# Raspberry_pi_shild_v1-.net
KiCad netlist of a schematic drawn in EAGLE
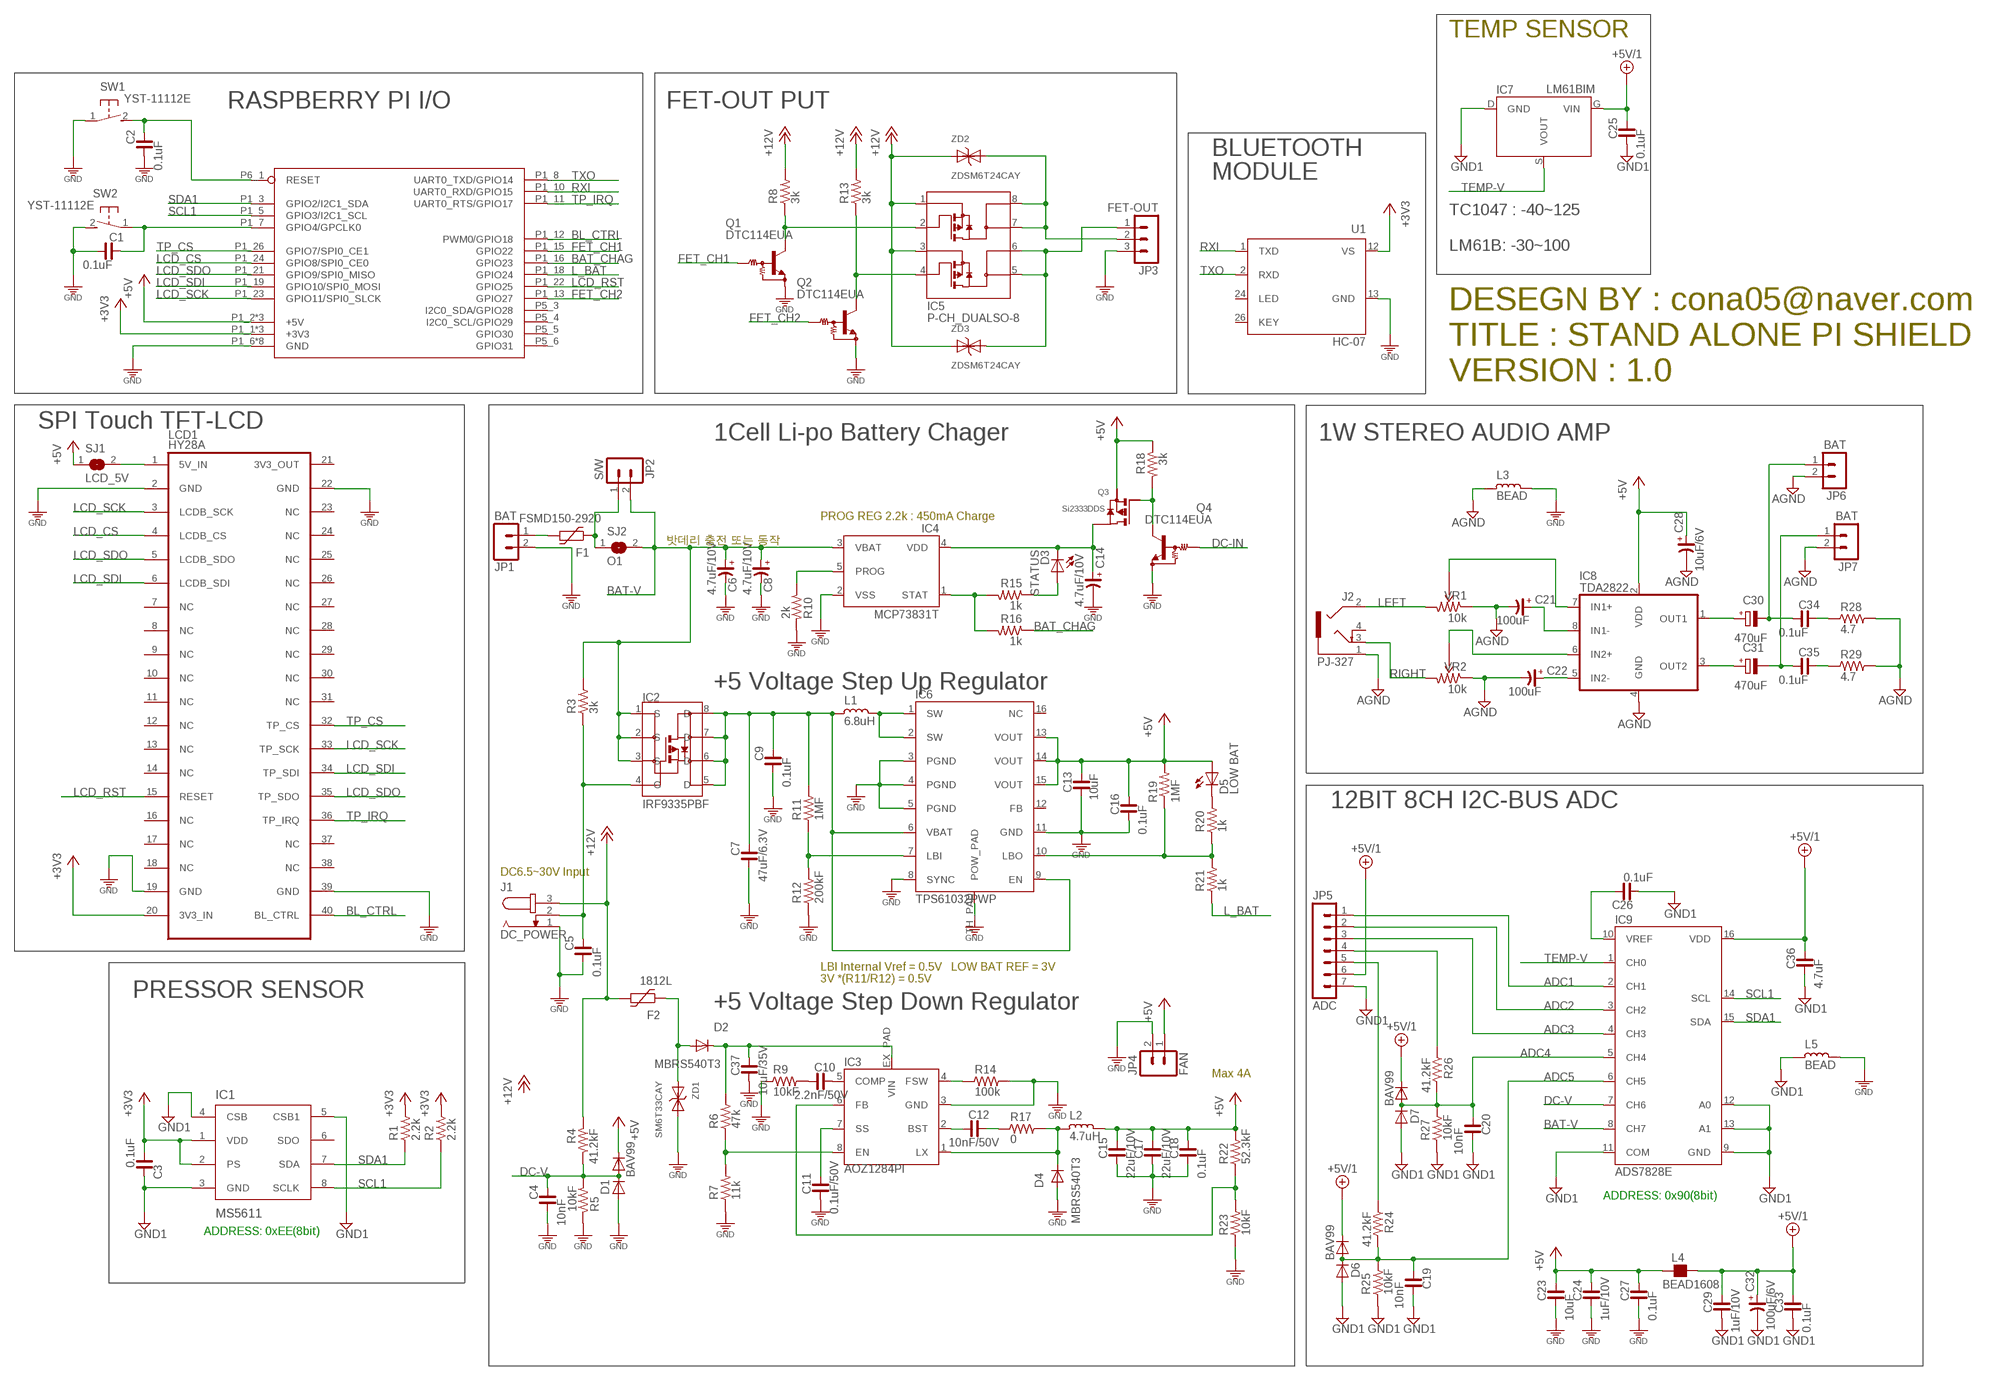
[diagram p0: schematic, sheet 1]

(export (version "E")
  (design (tool "Eeschema 10.0.6"))
  (components
    (comp (ref "C1")
      (value "0.1uF")
      (footprint "eagle-import:C0603")
      (libsource (lib "eagle-import") (part "C_0603"))
    )
    (comp (ref "C2")
      (value "0.1uF")
      (footprint "eagle-import:C0603")
      (libsource (lib "eagle-import") (part "C_0603"))
    )
    (comp (ref "C3")
      (value "0.1uF")
      (footprint "eagle-import:C0603")
      (libsource (lib "eagle-import") (part "C_0603"))
    )
    (comp (ref "C4")
      (value "10nF")
      (footprint "eagle-import:C0603")
      (libsource (lib "eagle-import") (part "C_0603"))
    )
    (comp (ref "C5")
      (value "0.1uF")
      (footprint "eagle-import:C0603")
      (libsource (lib "eagle-import") (part "C_0603"))
    )
    (comp (ref "C6")
      (value "4.7uF/10V")
      (footprint "eagle-import:C3216-18_T")
      (libsource (lib "eagle-import") (part "CP_3216-18"))
    )
    (comp (ref "C7")
      (value "47uF/6.3V")
      (footprint "eagle-import:C3216")
      (libsource (lib "eagle-import") (part "C_3216"))
    )
    (comp (ref "C8")
      (value "4.7uF/10V")
      (footprint "eagle-import:C3216-18_T")
      (libsource (lib "eagle-import") (part "CP_3216-18"))
    )
    (comp (ref "C9")
      (value "0.1uF")
      (footprint "eagle-import:C0603")
      (libsource (lib "eagle-import") (part "C_0603"))
    )
    (comp (ref "C10")
      (value "2.2nF/50V")
      (footprint "eagle-import:C0603")
      (libsource (lib "eagle-import") (part "C_0603"))
    )
    (comp (ref "C11")
      (value "0.1uF/50V")
      (footprint "eagle-import:C0603")
      (libsource (lib "eagle-import") (part "C_0603"))
    )
    (comp (ref "C12")
      (value "10nF/50V")
      (footprint "eagle-import:C0603")
      (libsource (lib "eagle-import") (part "C_0603"))
    )
    (comp (ref "C13")
      (value "10uF")
      (footprint "eagle-import:C2012")
      (libsource (lib "eagle-import") (part "C_2012"))
    )
    (comp (ref "C14")
      (value "4.7uF/10V")
      (footprint "eagle-import:C3216-18_T")
      (libsource (lib "eagle-import") (part "CP_3216-18"))
    )
    (comp (ref "C15")
      (value "22uF/10V")
      (footprint "eagle-import:C3216")
      (libsource (lib "eagle-import") (part "C_3216"))
    )
    (comp (ref "C16")
      (value "0.1uF")
      (footprint "eagle-import:C0603")
      (libsource (lib "eagle-import") (part "C_0603"))
    )
    (comp (ref "C17")
      (value "22uF/10V")
      (footprint "eagle-import:C3216")
      (libsource (lib "eagle-import") (part "C_3216"))
    )
    (comp (ref "C18")
      (value "0.1uF")
      (footprint "eagle-import:C0603")
      (libsource (lib "eagle-import") (part "C_0603"))
    )
    (comp (ref "C19")
      (value "10nF")
      (footprint "eagle-import:C0603")
      (libsource (lib "eagle-import") (part "C_0603"))
    )
    (comp (ref "C20")
      (value "10nF")
      (footprint "eagle-import:C0603")
      (libsource (lib "eagle-import") (part "C_0603"))
    )
    (comp (ref "C21")
      (value "100uF")
      (footprint "eagle-import:C3528-21_T")
      (libsource (lib "eagle-import") (part "CP_3528-21"))
    )
    (comp (ref "C22")
      (value "100uF")
      (footprint "eagle-import:C3528-21_T")
      (libsource (lib "eagle-import") (part "CP_3528-21"))
    )
    (comp (ref "C23")
      (value "10uF")
      (footprint "eagle-import:C0805")
      (libsource (lib "eagle-import") (part "C_0805"))
    )
    (comp (ref "C24")
      (value "1uF/10V")
      (footprint "eagle-import:C0603")
      (libsource (lib "eagle-import") (part "C_0603"))
    )
    (comp (ref "C25")
      (value "0.1uF")
      (footprint "eagle-import:C0603")
      (libsource (lib "eagle-import") (part "C_0603"))
    )
    (comp (ref "C26")
      (value "0.1uF")
      (footprint "eagle-import:C0603")
      (libsource (lib "eagle-import") (part "C_0603"))
    )
    (comp (ref "C27")
      (value "0.1uF")
      (footprint "eagle-import:C0603")
      (libsource (lib "eagle-import") (part "C_0603"))
    )
    (comp (ref "C28")
      (value "10uF/6V")
      (footprint "eagle-import:C3216-18_T")
      (libsource (lib "eagle-import") (part "CP_3216-18"))
    )
    (comp (ref "C29")
      (value "1uF/10V")
      (footprint "eagle-import:C0603")
      (libsource (lib "eagle-import") (part "C_0603"))
    )
    (comp (ref "C30")
      (value "470uF")
      (footprint "eagle-import:D_7343-31W")
      (libsource (lib "eagle-import") (part "CPOL-EUD/7343-31W"))
    )
    (comp (ref "C31")
      (value "470uF")
      (footprint "eagle-import:D_7343-31W")
      (libsource (lib "eagle-import") (part "CPOL-EUD/7343-31W"))
    )
    (comp (ref "C32")
      (value "100uF/6V")
      (footprint "eagle-import:C3528-21_T")
      (libsource (lib "eagle-import") (part "CP_3528-21"))
    )
    (comp (ref "C33")
      (value "0.1uF")
      (footprint "eagle-import:C0603")
      (libsource (lib "eagle-import") (part "C_0603"))
    )
    (comp (ref "C34")
      (value "0.1uF")
      (footprint "eagle-import:C0603")
      (libsource (lib "eagle-import") (part "C_0603"))
    )
    (comp (ref "C35")
      (value "0.1uF")
      (footprint "eagle-import:C0603")
      (libsource (lib "eagle-import") (part "C_0603"))
    )
    (comp (ref "C36")
      (value "4.7uF")
      (footprint "eagle-import:C0805")
      (libsource (lib "eagle-import") (part "C_0805"))
    )
    (comp (ref "C37")
      (value "10uF/35V")
      (footprint "eagle-import:C3225")
      (libsource (lib "eagle-import") (part "C_3225"))
    )
    (comp (ref "D1")
      (value "BAV99")
      (footprint "eagle-import:SOT23")
      (libsource (lib "eagle-import") (part "BAV99"))
    )
    (comp (ref "D2")
      (value "MBRS540T3")
      (footprint "eagle-import:SMC")
      (libsource (lib "eagle-import") (part "DIODE-SMC"))
    )
    (comp (ref "D3")
      (value "STATUS")
      (footprint "eagle-import:LED3MM")
      (libsource (lib "eagle-import") (part "LED3MM"))
    )
    (comp (ref "D4")
      (value "MBRS540T3")
      (footprint "eagle-import:SMC")
      (libsource (lib "eagle-import") (part "DIODE-SMC"))
    )
    (comp (ref "D5")
      (value "LOW BAT")
      (footprint "eagle-import:LED3MM")
      (libsource (lib "eagle-import") (part "LED3MM"))
    )
    (comp (ref "D6")
      (value "BAV99")
      (footprint "eagle-import:SOT23")
      (libsource (lib "eagle-import") (part "BAV99"))
    )
    (comp (ref "D7")
      (value "BAV99")
      (footprint "eagle-import:SOT23")
      (libsource (lib "eagle-import") (part "BAV99"))
    )
    (comp (ref "F1")
      (value "FSMD150-2920")
      (footprint "eagle-import:1812L")
      (libsource (lib "eagle-import") (part "1812L"))
    )
    (comp (ref "F2")
      (value "1812L")
      (footprint "eagle-import:1812L")
      (libsource (lib "eagle-import") (part "1812L"))
    )
    (comp (ref "IC1")
      (value "MS5611")
      (footprint "eagle-import:LCP8")
      (libsource (lib "eagle-import") (part "MS5611"))
    )
    (comp (ref "IC2")
      (value "IRF9335PBF")
      (footprint "eagle-import:SO08")
      (libsource (lib "eagle-import") (part "HEXFET_P"))
    )
    (comp (ref "IC3")
      (value "AOZ1284PI")
      (footprint "eagle-import:S08-EP1")
      (libsource (lib "eagle-import") (part "AOZ1284PI"))
    )
    (comp (ref "IC4")
      (value "MCP73831T")
      (footprint "eagle-import:SOT23-5L@1")
      (libsource (lib "eagle-import") (part "MCP73831T"))
    )
    (comp (ref "IC5")
      (value "P-CH_DUALSO-8")
      (footprint "eagle-import:SO08-1")
      (libsource (lib "eagle-import") (part "P-CH_DUALSO-8"))
    )
    (comp (ref "IC6")
      (value "TPS61032PWP")
      (footprint "eagle-import:R-PDSO-G16-TH_PAD")
      (libsource (lib "eagle-import") (part "TPS61032"))
    )
    (comp (ref "IC7")
      (value "LM61BIM")
      (footprint "eagle-import:SOT23")
      (libsource (lib "eagle-import") (part "LM61BIM"))
    )
    (comp (ref "IC8")
      (value "TDA2822")
      (footprint "eagle-import:SO08")
      (libsource (lib "eagle-import") (part "TDA2822"))
    )
    (comp (ref "IC9")
      (value "ADS7828E")
      (footprint "eagle-import:R-PDSO-G16")
      (libsource (lib "eagle-import") (part "ADS7828"))
    )
    (comp (ref "J1")
      (value "DC_POWER")
      (footprint "eagle-import:SPC4077")
      (libsource (lib "eagle-import") (part "JACK-PLUG0"))
    )
    (comp (ref "J2")
      (value "PJ-327")
      (footprint "eagle-import:PJ-327-2")
      (libsource (lib "eagle-import") (part "AUDIO_JACK2"))
    )
    (comp (ref "JP1")
      (value "BAT")
      (footprint "eagle-import:MA02-MOL-R")
      (libsource (lib "eagle-import") (part "MA02MOL-R"))
    )
    (comp (ref "JP2")
      (value "S/W")
      (footprint "eagle-import:MA02-MOL-R")
      (libsource (lib "eagle-import") (part "MA02MOL-R"))
    )
    (comp (ref "JP3")
      (value "FET-OUT")
      (footprint "eagle-import:MA03")
      (libsource (lib "eagle-import") (part "MA03-1DEF"))
    )
    (comp (ref "JP4")
      (value "FAN")
      (footprint "eagle-import:MA02-MOL-R")
      (libsource (lib "eagle-import") (part "MA02MOL-R"))
    )
    (comp (ref "JP5")
      (value "ADC")
      (footprint "eagle-import:MA07-1T")
      (libsource (lib "eagle-import") (part "MA07-1"))
    )
    (comp (ref "JP6")
      (value "BAT")
      (footprint "eagle-import:MA02-MOL-R")
      (libsource (lib "eagle-import") (part "MA02MOL-R"))
    )
    (comp (ref "JP7")
      (value "BAT")
      (footprint "eagle-import:MA02-MOL-R")
      (libsource (lib "eagle-import") (part "MA02MOL-R"))
    )
    (comp (ref "L1")
      (value "6.8uH")
      (footprint "eagle-import:L4545")
      (libsource (lib "eagle-import") (part "L_4545"))
    )
    (comp (ref "L2")
      (value "4.7uH")
      (footprint "eagle-import:L4545")
      (libsource (lib "eagle-import") (part "L_4545"))
    )
    (comp (ref "L3")
      (value "BEAD")
      (footprint "eagle-import:L0603")
      (libsource (lib "eagle-import") (part "L_0603"))
    )
    (comp (ref "L4")
      (value "BEAD1608")
      (footprint "eagle-import:L0603")
      (libsource (lib "eagle-import") (part "FB_0603"))
    )
    (comp (ref "L5")
      (value "BEAD")
      (footprint "eagle-import:L0603")
      (libsource (lib "eagle-import") (part "L_0603"))
    )
    (comp (ref "LCD1")
      (value "HY28A")
      (footprint "eagle-import:HY28A")
      (libsource (lib "eagle-import") (part "HY28A"))
    )
    (comp (ref "Q1")
      (value "DTC114EUA")
      (footprint "eagle-import:SC59-BEC")
      (libsource (lib "eagle-import") (part "DTC114EUA"))
    )
    (comp (ref "Q2")
      (value "DTC114EUA")
      (footprint "eagle-import:SC59-BEC")
      (libsource (lib "eagle-import") (part "DTC114EUA"))
    )
    (comp (ref "Q3")
      (value "Si2333DDS")
      (footprint "eagle-import:SOT23")
      (libsource (lib "eagle-import") (part "P-FET"))
    )
    (comp (ref "Q4")
      (value "DTC114EUA")
      (footprint "eagle-import:SC59-BEC")
      (libsource (lib "eagle-import") (part "DTC114EUA"))
    )
    (comp (ref "R1")
      (value "2.2k")
      (footprint "eagle-import:R0603")
      (libsource (lib "eagle-import") (part "R_0603"))
    )
    (comp (ref "R2")
      (value "2.2k")
      (footprint "eagle-import:R0603")
      (libsource (lib "eagle-import") (part "R_0603"))
    )
    (comp (ref "R3")
      (value "3k")
      (footprint "eagle-import:R0603")
      (libsource (lib "eagle-import") (part "R_0603"))
    )
    (comp (ref "R4")
      (value "41.2kF")
      (footprint "eagle-import:R0603")
      (libsource (lib "eagle-import") (part "R_0603"))
    )
    (comp (ref "R5")
      (value "10kF")
      (footprint "eagle-import:R0603")
      (libsource (lib "eagle-import") (part "R_0603"))
    )
    (comp (ref "R6")
      (value "47k")
      (footprint "eagle-import:R0603")
      (libsource (lib "eagle-import") (part "R_0603"))
    )
    (comp (ref "R7")
      (value "11k")
      (footprint "eagle-import:R0603")
      (libsource (lib "eagle-import") (part "R_0603"))
    )
    (comp (ref "R8")
      (value "3k")
      (footprint "eagle-import:R0603")
      (libsource (lib "eagle-import") (part "R_0603"))
    )
    (comp (ref "R9")
      (value "10kF")
      (footprint "eagle-import:R0603")
      (libsource (lib "eagle-import") (part "R_0603"))
    )
    (comp (ref "R10")
      (value "2k")
      (footprint "eagle-import:R0603")
      (libsource (lib "eagle-import") (part "R_0603"))
    )
    (comp (ref "R11")
      (value "1MF")
      (footprint "eagle-import:R0603")
      (libsource (lib "eagle-import") (part "R_0603"))
    )
    (comp (ref "R12")
      (value "200kF")
      (footprint "eagle-import:R0603")
      (libsource (lib "eagle-import") (part "R_0603"))
    )
    (comp (ref "R13")
      (value "3k")
      (footprint "eagle-import:R0603")
      (libsource (lib "eagle-import") (part "R_0603"))
    )
    (comp (ref "R14")
      (value "100k")
      (footprint "eagle-import:R0603")
      (libsource (lib "eagle-import") (part "R_0603"))
    )
    (comp (ref "R15")
      (value "1k")
      (footprint "eagle-import:R0603")
      (libsource (lib "eagle-import") (part "R_0603"))
    )
    (comp (ref "R16")
      (value "1k")
      (footprint "eagle-import:R0603")
      (libsource (lib "eagle-import") (part "R_0603"))
    )
    (comp (ref "R17")
      (value "0")
      (footprint "eagle-import:R0603")
      (libsource (lib "eagle-import") (part "R_0603"))
    )
    (comp (ref "R18")
      (value "3k")
      (footprint "eagle-import:R0603")
      (libsource (lib "eagle-import") (part "R_0603"))
    )
    (comp (ref "R19")
      (value "1MF")
      (footprint "eagle-import:R0603")
      (libsource (lib "eagle-import") (part "R-US_R1608"))
    )
    (comp (ref "R20")
      (value "1k")
      (footprint "eagle-import:R0603")
      (libsource (lib "eagle-import") (part "R_0603"))
    )
    (comp (ref "R21")
      (value "1k")
      (footprint "eagle-import:R0603")
      (libsource (lib "eagle-import") (part "R_0603"))
    )
    (comp (ref "R22")
      (value "52.3kF")
      (footprint "eagle-import:R0603")
      (libsource (lib "eagle-import") (part "R_0603"))
    )
    (comp (ref "R23")
      (value "10kF")
      (footprint "eagle-import:R0603")
      (libsource (lib "eagle-import") (part "R_0603"))
    )
    (comp (ref "R24")
      (value "41.2kF")
      (footprint "eagle-import:R0603")
      (libsource (lib "eagle-import") (part "R_0603"))
    )
    (comp (ref "R25")
      (value "10kF")
      (footprint "eagle-import:R0603")
      (libsource (lib "eagle-import") (part "R_0603"))
    )
    (comp (ref "R26")
      (value "41.2kF")
      (footprint "eagle-import:R0603")
      (libsource (lib "eagle-import") (part "R_0603"))
    )
    (comp (ref "R27")
      (value "10kF")
      (footprint "eagle-import:R0603")
      (libsource (lib "eagle-import") (part "R_0603"))
    )
    (comp (ref "R28")
      (value "4.7")
      (footprint "eagle-import:R0603")
      (libsource (lib "eagle-import") (part "R_0603"))
    )
    (comp (ref "R29")
      (value "4.7")
      (footprint "eagle-import:R0603")
      (libsource (lib "eagle-import") (part "R_0603"))
    )
    (comp (ref "SJ1")
      (value "LCD_5V")
      (footprint "eagle-import:SJ")
      (libsource (lib "eagle-import") (part "SJ"))
    )
    (comp (ref "SJ2") (value "O1") (footprint "eagle-import:SJ") (libsource (lib "eagle-import") (part "SJ")))
    (comp (ref "SW1")
      (value "YST-11112E")
      (footprint "eagle-import:YST-1112E")
      (libsource (lib "eagle-import") (part "YST-11112E"))
    )
    (comp (ref "SW2")
      (value "YST-11112E")
      (footprint "eagle-import:YST-1112E")
      (libsource (lib "eagle-import") (part "YST-11112E"))
    )
    (comp (ref "U$1")
      (value "RPI-B-V2NO_SHIELD")
      (footprint "eagle-import:RPI-B-V2")
      (libsource (lib "eagle-import") (part "RPI-B-V2NO_SHIELD"))
    )
    (comp (ref "U1")
      (value "HC-07")
      (footprint "eagle-import:HC-06")
      (libsource (lib "eagle-import") (part "HC-06_MODULEFULL"))
    )
    (comp (ref "VR1")
      (value "10k")
      (footprint "eagle-import:R-TRIMMER-3313J")
      (libsource (lib "eagle-import") (part "R-TRIMMER-SMD3313"))
    )
    (comp (ref "VR2")
      (value "10k")
      (footprint "eagle-import:R-TRIMMER-3313J")
      (libsource (lib "eagle-import") (part "R-TRIMMER-SMD3313"))
    )
    (comp (ref "ZD1")
      (value "SM6T33CAY")
      (footprint "eagle-import:SMB")
      (libsource (lib "eagle-import") (part "ZDSM6T33CAY"))
    )
    (comp (ref "ZD2")
      (value "ZDSM6T24CAY")
      (footprint "eagle-import:SMB")
      (libsource (lib "eagle-import") (part "ZDSM6T33CAY"))
    )
    (comp (ref "ZD3")
      (value "ZDSM6T24CAY")
      (footprint "eagle-import:SMB")
      (libsource (lib "eagle-import") (part "ZDSM6T33CAY"))
    )
  )
  (nets
    (net (code "1") (name "+3V3") (class "Default")
      (node (ref "C3") (pin "2") (pinfunction "2_2") (pintype "passive"))
      (node (ref "IC1") (pin "1") (pinfunction "VDD_1") (pintype "power_in"))
      (node (ref "IC1") (pin "2") (pinfunction "PS_2") (pintype "power_in"))
      (node (ref "LCD1") (pin "20") (pinfunction "3V3_IN_20") (pintype "passive"))
      (node (ref "R1") (pin "2") (pinfunction "2_2") (pintype "passive"))
      (node (ref "R2") (pin "2") (pinfunction "2_2") (pintype "passive"))
      (node (ref "U$1") (pin "P1_1") (pinfunction "+3V3_P1_1") (pintype "power_in"))
      (node (ref "U$1") (pin "P1_17") (pinfunction "+3V3_P1_17") (pintype "power_in"))
      (node (ref "U$1") (pin "P5_2") (pinfunction "+3V3_P5_2") (pintype "power_in"))
      (node (ref "U1") (pin "12") (pinfunction "VS_12") (pintype "power_in"))
    )
    (net (code "2") (name "+5V") (class "Default")
      (node (ref "C13") (pin "1") (pinfunction "1_1") (pintype "passive"))
      (node (ref "C15") (pin "1") (pinfunction "1_1") (pintype "passive"))
      (node (ref "C16") (pin "1") (pinfunction "1_1") (pintype "passive"))
      (node (ref "C17") (pin "1") (pinfunction "1_1") (pintype "passive"))
      (node (ref "C18") (pin "1") (pinfunction "1_1") (pintype "passive"))
      (node (ref "C23") (pin "1") (pinfunction "1_1") (pintype "passive"))
      (node (ref "C24") (pin "1") (pinfunction "1_1") (pintype "passive"))
      (node (ref "C27") (pin "1") (pinfunction "1_1") (pintype "passive"))
      (node (ref "C28") (pin "+") (pinfunction "+_+") (pintype "passive"))
      (node (ref "D1") (pin "S") (pinfunction "C_S") (pintype "passive"))
      (node (ref "D5") (pin "A") (pinfunction "A_A") (pintype "passive"))
      (node (ref "IC6") (pin "13") (pinfunction "VOUT_13") (pintype "passive"))
      (node (ref "IC6") (pin "14") (pinfunction "VOUT_14") (pintype "passive"))
      (node (ref "IC6") (pin "15") (pinfunction "VOUT_15") (pintype "passive"))
      (node (ref "IC8") (pin "2") (pinfunction "VDD_2") (pintype "power_in"))
      (node (ref "JP4") (pin "1") (pinfunction "1_1") (pintype "passive"))
      (node (ref "L2") (pin "1") (pinfunction "1_1") (pintype "passive"))
      (node (ref "L4") (pin "1") (pinfunction "1_1") (pintype "passive"))
      (node (ref "Q3") (pin "S") (pinfunction "SOURCE_S") (pintype "bidirectional"))
      (node (ref "R18") (pin "1") (pinfunction "1_1") (pintype "passive"))
      (node (ref "R19") (pin "2") (pinfunction "2_2") (pintype "passive"))
      (node (ref "R22") (pin "2") (pinfunction "2_2") (pintype "passive"))
      (node (ref "SJ1") (pin "1") (pinfunction "1_1") (pintype "passive"))
      (node (ref "U$1") (pin "P1_2") (pinfunction "+5V_P1_2") (pintype "power_in"))
      (node (ref "U$1") (pin "P1_4") (pinfunction "+5V_P1_4") (pintype "power_in"))
      (node (ref "U$1") (pin "P5_1") (pinfunction "+5V_P5_1") (pintype "power_in"))
    )
    (net (code "3") (name "+5V{slash}1") (class "Default")
      (node (ref "C25") (pin "1") (pinfunction "1_1") (pintype "passive"))
      (node (ref "C29") (pin "1") (pinfunction "1_1") (pintype "passive"))
      (node (ref "C32") (pin "+") (pinfunction "+_+") (pintype "passive"))
      (node (ref "C33") (pin "1") (pinfunction "1_1") (pintype "passive"))
      (node (ref "C36") (pin "1") (pinfunction "1_1") (pintype "passive"))
      (node (ref "D6") (pin "S") (pinfunction "C_S") (pintype "passive"))
      (node (ref "D7") (pin "S") (pinfunction "C_S") (pintype "passive"))
      (node (ref "IC7") (pin "G") (pinfunction "VIN_G") (pintype "power_in"))
      (node (ref "IC9") (pin "16") (pinfunction "VDD_16") (pintype "power_in"))
      (node (ref "JP5") (pin "6") (pinfunction "6_6") (pintype "passive"))
      (node (ref "L4") (pin "2") (pinfunction "2_2") (pintype "passive"))
    )
    (net (code "4") (name "+12V") (class "Default")
      (node (ref "F2") (pin "P$2") (pinfunction "2_P$2") (pintype "passive"))
      (node (ref "IC5") (pin "1") (pinfunction "1_1") (pintype "power_in"))
      (node (ref "IC5") (pin "3") (pinfunction "3_3") (pintype "power_in"))
      (node (ref "J1") (pin "3") (pinfunction "3_3") (pintype "passive"))
      (node (ref "R13") (pin "2") (pinfunction "2_2") (pintype "passive"))
      (node (ref "R4") (pin "1") (pinfunction "1_1") (pintype "passive"))
      (node (ref "R8") (pin "2") (pinfunction "2_2") (pintype "passive"))
      (node (ref "ZD2") (pin "A") (pinfunction "A_A") (pintype "passive"))
      (node (ref "ZD3") (pin "A") (pinfunction "A_A") (pintype "passive"))
    )
    (net (code "5") (name "/ADC1") (class "Default")
      (node (ref "IC9") (pin "2") (pinfunction "CH1_2") (pintype "input"))
      (node (ref "JP5") (pin "1") (pinfunction "1_1") (pintype "passive"))
    )
    (net (code "6") (name "/ADC2") (class "Default")
      (node (ref "IC9") (pin "3") (pinfunction "CH2_3") (pintype "input"))
      (node (ref "JP5") (pin "2") (pinfunction "2_2") (pintype "passive"))
    )
    (net (code "7") (name "/ADC3") (class "Default")
      (node (ref "IC9") (pin "4") (pinfunction "CH3_4") (pintype "input"))
      (node (ref "JP5") (pin "3") (pinfunction "3_3") (pintype "passive"))
    )
    (net (code "8") (name "/ADC4") (class "Default")
      (node (ref "C20") (pin "1") (pinfunction "1_1") (pintype "passive"))
      (node (ref "D7") (pin "D") (pinfunction "AC_D") (pintype "passive"))
      (node (ref "IC9") (pin "5") (pinfunction "CH4_5") (pintype "input"))
      (node (ref "R26") (pin "2") (pinfunction "2_2") (pintype "passive"))
      (node (ref "R27") (pin "2") (pinfunction "2_2") (pintype "passive"))
    )
    (net (code "9") (name "/ADC5") (class "Default")
      (node (ref "C19") (pin "1") (pinfunction "1_1") (pintype "passive"))
      (node (ref "D6") (pin "D") (pinfunction "AC_D") (pintype "passive"))
      (node (ref "IC9") (pin "6") (pinfunction "CH5_6") (pintype "input"))
      (node (ref "R24") (pin "2") (pinfunction "2_2") (pintype "passive"))
      (node (ref "R25") (pin "2") (pinfunction "2_2") (pintype "passive"))
    )
    (net (code "10") (name "/BAT-V") (class "Default")
      (node (ref "C6") (pin "+") (pinfunction "+_+") (pintype "passive"))
      (node (ref "C8") (pin "+") (pinfunction "+_+") (pintype "passive"))
      (node (ref "IC2") (pin "1") (pinfunction "S_1") (pintype "passive"))
      (node (ref "IC2") (pin "2") (pinfunction "S_2") (pintype "passive"))
      (node (ref "IC2") (pin "3") (pinfunction "S_3") (pintype "passive"))
      (node (ref "IC4") (pin "3") (pinfunction "VBAT_3") (pintype "power_in"))
      (node (ref "IC9") (pin "8") (pinfunction "CH7_8") (pintype "input"))
      (node (ref "JP2") (pin "2") (pinfunction "2_2") (pintype "passive"))
      (node (ref "R3") (pin "2") (pinfunction "2_2") (pintype "passive"))
      (node (ref "SJ2") (pin "2") (pinfunction "2_2") (pintype "passive"))
    )
    (net (code "11") (name "/BAT_CHAG") (class "Default")
      (node (ref "R16") (pin "1") (pinfunction "1_1") (pintype "passive"))
      (node (ref "U$1") (pin "P1_16") (pinfunction "GPIO23_P1_16") (pintype "bidirectional"))
    )
    (net (code "12") (name "/BL_CTRL") (class "Default")
      (node (ref "LCD1") (pin "40") (pinfunction "BL_CTRL_40") (pintype "passive"))
      (node (ref "U$1") (pin "P1_12") (pinfunction "PWM0/GPIO18_P1_12") (pintype "bidirectional"))
    )
    (net (code "13") (name "/DC-IN") (class "Default")
      (node (ref "D2") (pin "A") (pinfunction "A_A") (pintype "passive"))
      (node (ref "F2") (pin "P$1") (pinfunction "1_P$1") (pintype "passive"))
      (node (ref "Q4") (pin "2") (pinfunction "IN_2") (pintype "passive"))
      (node (ref "ZD1") (pin "A") (pinfunction "A_A") (pintype "passive"))
    )
    (net (code "14") (name "/DC-V") (class "Default")
      (node (ref "C4") (pin "1") (pinfunction "1_1") (pintype "passive"))
      (node (ref "D1") (pin "D") (pinfunction "AC_D") (pintype "passive"))
      (node (ref "IC9") (pin "7") (pinfunction "CH6_7") (pintype "input"))
      (node (ref "R4") (pin "2") (pinfunction "2_2") (pintype "passive"))
      (node (ref "R5") (pin "2") (pinfunction "2_2") (pintype "passive"))
    )
    (net (code "15") (name "/FET_CH1") (class "Default")
      (node (ref "Q1") (pin "2") (pinfunction "IN_2") (pintype "passive"))
      (node (ref "U$1") (pin "P1_15") (pinfunction "GPIO22_P1_15") (pintype "bidirectional"))
    )
    (net (code "16") (name "/FET_CH2") (class "Default")
      (node (ref "Q2") (pin "2") (pinfunction "IN_2") (pintype "passive"))
      (node (ref "U$1") (pin "P1_13") (pinfunction "GPIO27_P1_13") (pintype "bidirectional"))
    )
    (net (code "17") (name "/GPIO30") (class "Default")
      (node (ref "U$1") (pin "P5_5") (pinfunction "GPIO30_P5_5") (pintype "power_in"))
    )
    (net (code "18") (name "/GPIO31") (class "Default")
      (node (ref "U$1") (pin "P5_6") (pinfunction "GPIO31_P5_6") (pintype "power_in"))
    )
    (net (code "19") (name "/I2C0_SCL{slash}GPIO29") (class "Default")
      (node (ref "U$1") (pin "P5_4") (pinfunction "I2C0_SCL/GPIO29_P5_4") (pintype "power_in"))
    )
    (net (code "20") (name "/I2C0_SDA{slash}GPIO28") (class "Default")
      (node (ref "U$1") (pin "P5_3") (pinfunction "I2C0_SDA/GPIO28_P5_3") (pintype "power_in"))
    )
    (net (code "21") (name "/LCD_CS") (class "Default")
      (node (ref "LCD1") (pin "4") (pinfunction "LCDB_CS_4") (pintype "passive"))
      (node (ref "U$1") (pin "P1_24") (pinfunction "GPIO8/SPI0_CE0_P1_24") (pintype "bidirectional"))
    )
    (net (code "22") (name "/LCD_RST") (class "Default")
      (node (ref "LCD1") (pin "15") (pinfunction "RESET_15") (pintype "passive"))
      (node (ref "U$1") (pin "P1_22") (pinfunction "GPIO25_P1_22") (pintype "bidirectional"))
    )
    (net (code "23") (name "/LCD_SCK") (class "Default")
      (node (ref "LCD1") (pin "3") (pinfunction "LCDB_SCK_3") (pintype "passive"))
      (node (ref "LCD1") (pin "33") (pinfunction "TP_SCK_33") (pintype "passive"))
      (node (ref "U$1") (pin "P1_23") (pinfunction "GPIO11/SPI0_SLCK_P1_23") (pintype "bidirectional"))
    )
    (net (code "24") (name "/LCD_SDI") (class "Default")
      (node (ref "LCD1") (pin "34") (pinfunction "TP_SDI_34") (pintype "passive"))
      (node (ref "LCD1") (pin "6") (pinfunction "LCDB_SDI_6") (pintype "passive"))
      (node (ref "U$1") (pin "P1_19") (pinfunction "GPIO10/SPI0_MOSI_P1_19") (pintype "bidirectional"))
    )
    (net (code "25") (name "/LCD_SDO") (class "Default")
      (node (ref "LCD1") (pin "35") (pinfunction "TP_SDO_35") (pintype "passive"))
      (node (ref "LCD1") (pin "5") (pinfunction "LCDB_SDO_5") (pintype "passive"))
      (node (ref "U$1") (pin "P1_21") (pinfunction "GPIO9/SPI0_MISO_P1_21") (pintype "bidirectional"))
    )
    (net (code "26") (name "/LEFT") (class "Default")
      (node (ref "J2") (pin "2") (pinfunction "2_2") (pintype "passive"))
      (node (ref "VR1") (pin "3") (pinfunction "3_3") (pintype "passive"))
    )
    (net (code "27") (name "/L_BAT") (class "Default")
      (node (ref "R21") (pin "1") (pinfunction "1_1") (pintype "passive"))
      (node (ref "U$1") (pin "P1_18") (pinfunction "GPIO24_P1_18") (pintype "bidirectional"))
    )
    (net (code "28") (name "/RIGHT") (class "Default")
      (node (ref "J2") (pin "3") (pinfunction "3_3") (pintype "passive"))
      (node (ref "VR2") (pin "3") (pinfunction "3_3") (pintype "passive"))
    )
    (net (code "29") (name "/RXI") (class "Default")
      (node (ref "U$1") (pin "P1_10") (pinfunction "UART0_RXD/GPIO15_P1_10") (pintype "bidirectional"))
      (node (ref "U1") (pin "1") (pinfunction "TXD_1") (pintype "output"))
    )
    (net (code "30") (name "/SCL1") (class "Default")
      (node (ref "IC1") (pin "8") (pinfunction "SCLK_8") (pintype "input"))
      (node (ref "IC9") (pin "14") (pinfunction "SCL_14") (pintype "bidirectional"))
      (node (ref "R2") (pin "1") (pinfunction "1_1") (pintype "passive"))
      (node (ref "U$1") (pin "P1_5") (pinfunction "GPIO3/I2C1_SCL_P1_5") (pintype "bidirectional"))
    )
    (net (code "31") (name "/SDA1") (class "Default")
      (node (ref "IC1") (pin "7") (pinfunction "SDA_7") (pintype "bidirectional"))
      (node (ref "IC9") (pin "15") (pinfunction "SDA_15") (pintype "output"))
      (node (ref "R1") (pin "1") (pinfunction "1_1") (pintype "passive"))
      (node (ref "U$1") (pin "P1_3") (pinfunction "GPIO2/I2C1_SDA_P1_3") (pintype "bidirectional"))
    )
    (net (code "32") (name "/TEMP-V") (class "Default")
      (node (ref "IC7") (pin "S") (pinfunction "VOUT_S") (pintype "output"))
      (node (ref "IC9") (pin "1") (pinfunction "CH0_1") (pintype "input"))
    )
    (net (code "33") (name "/TP_CS") (class "Default")
      (node (ref "LCD1") (pin "32") (pinfunction "TP_CS_32") (pintype "passive"))
      (node (ref "U$1") (pin "P1_26") (pinfunction "GPIO7/SPI0_CE1_P1_26") (pintype "bidirectional"))
    )
    (net (code "34") (name "/TP_IRQ") (class "Default")
      (node (ref "LCD1") (pin "36") (pinfunction "TP_IRQ_36") (pintype "passive"))
      (node (ref "U$1") (pin "P1_11") (pinfunction "UART0_RTS/GPIO17_P1_11") (pintype "bidirectional"))
    )
    (net (code "35") (name "/TXO") (class "Default")
      (node (ref "U$1") (pin "P1_8") (pinfunction "UART0_TXD/GPIO14_P1_8") (pintype "bidirectional"))
      (node (ref "U1") (pin "2") (pinfunction "RXD_2") (pintype "input"))
    )
    (net (code "36") (name "AGND") (class "Default")
      (node (ref "C21") (pin "-") (pinfunction "-_-") (pintype "passive"))
      (node (ref "C22") (pin "-") (pinfunction "-_-") (pintype "passive"))
      (node (ref "C28") (pin "-") (pinfunction "-_-") (pintype "passive"))
      (node (ref "IC8") (pin "4") (pinfunction "GND_4") (pintype "power_in"))
      (node (ref "J2") (pin "1") (pinfunction "1_1") (pintype "passive"))
      (node (ref "JP6") (pin "2") (pinfunction "2_2") (pintype "passive"))
      (node (ref "JP7") (pin "2") (pinfunction "2_2") (pintype "passive"))
      (node (ref "L3") (pin "2") (pinfunction "2_2") (pintype "passive"))
      (node (ref "R28") (pin "2") (pinfunction "2_2") (pintype "passive"))
      (node (ref "R29") (pin "2") (pinfunction "2_2") (pintype "passive"))
      (node (ref "VR1") (pin "1") (pinfunction "1_1") (pintype "passive"))
      (node (ref "VR2") (pin "1") (pinfunction "1_1") (pintype "passive"))
    )
    (net (code "37") (name "GND") (class "Default")
      (node (ref "C1") (pin "2") (pinfunction "2_2") (pintype "passive"))
      (node (ref "C11") (pin "2") (pinfunction "2_2") (pintype "passive"))
      (node (ref "C13") (pin "2") (pinfunction "2_2") (pintype "passive"))
      (node (ref "C14") (pin "-") (pinfunction "-_-") (pintype "passive"))
      (node (ref "C15") (pin "2") (pinfunction "2_2") (pintype "passive"))
      (node (ref "C16") (pin "2") (pinfunction "2_2") (pintype "passive"))
      (node (ref "C17") (pin "2") (pinfunction "2_2") (pintype "passive"))
      (node (ref "C18") (pin "2") (pinfunction "2_2") (pintype "passive"))
      (node (ref "C2") (pin "2") (pinfunction "2_2") (pintype "passive"))
      (node (ref "C23") (pin "2") (pinfunction "2_2") (pintype "passive"))
      (node (ref "C24") (pin "2") (pinfunction "2_2") (pintype "passive"))
      (node (ref "C27") (pin "2") (pinfunction "2_2") (pintype "passive"))
      (node (ref "C37") (pin "2") (pinfunction "2_2") (pintype "passive"))
      (node (ref "C4") (pin "2") (pinfunction "2_2") (pintype "passive"))
      (node (ref "C5") (pin "2") (pinfunction "2_2") (pintype "passive"))
      (node (ref "C6") (pin "-") (pinfunction "-_-") (pintype "passive"))
      (node (ref "C7") (pin "2") (pinfunction "2_2") (pintype "passive"))
      (node (ref "C8") (pin "-") (pinfunction "-_-") (pintype "passive"))
      (node (ref "C9") (pin "2") (pinfunction "2_2") (pintype "passive"))
      (node (ref "D1") (pin "G") (pinfunction "A_G") (pintype "passive"))
      (node (ref "D4") (pin "A") (pinfunction "A_A") (pintype "passive"))
      (node (ref "IC3") (pin "3") (pinfunction "GND_3") (pintype "power_in"))
      (node (ref "IC4") (pin "2") (pinfunction "VSS_2") (pintype "power_in"))
      (node (ref "IC6") (pin "11") (pinfunction "GND_11") (pintype "power_in"))
      (node (ref "IC6") (pin "3") (pinfunction "PGND_3") (pintype "power_in"))
      (node (ref "IC6") (pin "4") (pinfunction "PGND_4") (pintype "power_in"))
      (node (ref "IC6") (pin "5") (pinfunction "PGND_5") (pintype "power_in"))
      (node (ref "IC6") (pin "8") (pinfunction "SYNC_8") (pintype "passive"))
      (node (ref "IC6") (pin "TH_PAD") (pinfunction "POW_PAD_TH_PAD") (pintype "power_in"))
      (node (ref "J1") (pin "1") (pinfunction "1_1") (pintype "passive"))
      (node (ref "JP1") (pin "2") (pinfunction "2_2") (pintype "passive"))
      (node (ref "JP3") (pin "3") (pinfunction "3_3") (pintype "passive"))
      (node (ref "JP4") (pin "2") (pinfunction "2_2") (pintype "passive"))
      (node (ref "L3") (pin "1") (pinfunction "1_1") (pintype "passive"))
      (node (ref "L5") (pin "1") (pinfunction "1_1") (pintype "passive"))
      (node (ref "LCD1") (pin "19") (pinfunction "GND_19") (pintype "power_in"))
      (node (ref "LCD1") (pin "2") (pinfunction "GND_2") (pintype "power_in"))
      (node (ref "LCD1") (pin "22") (pinfunction "GND_22") (pintype "power_in"))
      (node (ref "LCD1") (pin "39") (pinfunction "GND_39") (pintype "power_in"))
      (node (ref "Q1") (pin "1") (pinfunction "GND_1") (pintype "passive"))
      (node (ref "Q2") (pin "1") (pinfunction "GND_1") (pintype "passive"))
      (node (ref "Q4") (pin "1") (pinfunction "GND_1") (pintype "passive"))
      (node (ref "R10") (pin "1") (pinfunction "1_1") (pintype "passive"))
      (node (ref "R12") (pin "1") (pinfunction "1_1") (pintype "passive"))
      (node (ref "R14") (pin "2") (pinfunction "2_2") (pintype "passive"))
      (node (ref "R23") (pin "1") (pinfunction "1_1") (pintype "passive"))
      (node (ref "R5") (pin "1") (pinfunction "1_1") (pintype "passive"))
      (node (ref "R7") (pin "1") (pinfunction "1_1") (pintype "passive"))
      (node (ref "R9") (pin "1") (pinfunction "1_1") (pintype "passive"))
      (node (ref "SW1") (pin "1") (pinfunction "1_1") (pintype "passive"))
      (node (ref "SW2") (pin "2") (pinfunction "2_2") (pintype "passive"))
      (node (ref "U$1") (pin "P1_14") (pinfunction "GND_P1_14") (pintype "power_in"))
      (node (ref "U$1") (pin "P1_20") (pinfunction "GND_P1_20") (pintype "power_in"))
      (node (ref "U$1") (pin "P1_25") (pinfunction "GND_P1_25") (pintype "power_in"))
      (node (ref "U$1") (pin "P1_6") (pinfunction "GND_P1_6") (pintype "power_in"))
      (node (ref "U$1") (pin "P1_9") (pinfunction "GND_P1_9") (pintype "power_in"))
      (node (ref "U$1") (pin "P5_7") (pinfunction "GND_P5_7") (pintype "power_in"))
      (node (ref "U$1") (pin "P5_8") (pinfunction "GND_P5_8") (pintype "power_in"))
      (node (ref "U$1") (pin "P6_2") (pinfunction "GND_P6_2") (pintype "power_in"))
      (node (ref "U1") (pin "13") (pinfunction "GND_13") (pintype "power_in"))
      (node (ref "ZD1") (pin "C") (pinfunction "K_C") (pintype "passive"))
    )
    (net (code "38") (name "GND1") (class "Default")
      (node (ref "C19") (pin "2") (pinfunction "2_2") (pintype "passive"))
      (node (ref "C20") (pin "2") (pinfunction "2_2") (pintype "passive"))
      (node (ref "C25") (pin "2") (pinfunction "2_2") (pintype "passive"))
      (node (ref "C26") (pin "2") (pinfunction "2_2") (pintype "passive"))
      (node (ref "C29") (pin "2") (pinfunction "2_2") (pintype "passive"))
      (node (ref "C3") (pin "1") (pinfunction "1_1") (pintype "passive"))
      (node (ref "C32") (pin "-") (pinfunction "-_-") (pintype "passive"))
      (node (ref "C33") (pin "2") (pinfunction "2_2") (pintype "passive"))
      (node (ref "C36") (pin "2") (pinfunction "2_2") (pintype "passive"))
      (node (ref "D6") (pin "G") (pinfunction "A_G") (pintype "passive"))
      (node (ref "D7") (pin "G") (pinfunction "A_G") (pintype "passive"))
      (node (ref "IC1") (pin "3") (pinfunction "GND_3") (pintype "power_in"))
      (node (ref "IC1") (pin "4") (pinfunction "CSB_4") (pintype "input"))
      (node (ref "IC1") (pin "5") (pinfunction "CSB1_5") (pintype "input"))
      (node (ref "IC7") (pin "D") (pinfunction "GND_D") (pintype "power_in"))
      (node (ref "IC9") (pin "11") (pinfunction "COM_11") (pintype "power_in"))
      (node (ref "IC9") (pin "12") (pinfunction "A0_12") (pintype "bidirectional"))
      (node (ref "IC9") (pin "13") (pinfunction "A1_13") (pintype "bidirectional"))
      (node (ref "IC9") (pin "9") (pinfunction "GND_9") (pintype "power_in"))
      (node (ref "JP5") (pin "7") (pinfunction "7_7") (pintype "passive"))
      (node (ref "L5") (pin "2") (pinfunction "2_2") (pintype "passive"))
      (node (ref "R25") (pin "1") (pinfunction "1_1") (pintype "passive"))
      (node (ref "R27") (pin "1") (pinfunction "1_1") (pintype "passive"))
    )
    (net (code "39") (name "Net-(C10-Pad2)") (class "Default")
      (node (ref "C10") (pin "2") (pinfunction "2_2") (pintype "passive"))
      (node (ref "R9") (pin "2") (pinfunction "2_2") (pintype "passive"))
    )
    (net (code "40") (name "Net-(C12-Pad1)") (class "Default")
      (node (ref "C12") (pin "1") (pinfunction "1_1") (pintype "passive"))
      (node (ref "R17") (pin "1") (pinfunction "1_1") (pintype "passive"))
    )
    (net (code "41") (name "Net-(C30-Pad-)") (class "Default")
      (node (ref "C30") (pin "-") (pinfunction "-_-") (pintype "passive"))
      (node (ref "C34") (pin "2") (pinfunction "2_2") (pintype "passive"))
      (node (ref "JP6") (pin "1") (pinfunction "1_1") (pintype "passive"))
    )
    (net (code "42") (name "Net-(C31-Pad-)") (class "Default")
      (node (ref "C31") (pin "-") (pinfunction "-_-") (pintype "passive"))
      (node (ref "C35") (pin "2") (pinfunction "2_2") (pintype "passive"))
      (node (ref "JP7") (pin "1") (pinfunction "1_1") (pintype "passive"))
    )
    (net (code "43") (name "Net-(C34-Pad1)") (class "Default")
      (node (ref "C34") (pin "1") (pinfunction "1_1") (pintype "passive"))
      (node (ref "R28") (pin "1") (pinfunction "1_1") (pintype "passive"))
    )
    (net (code "44") (name "Net-(C35-Pad1)") (class "Default")
      (node (ref "C35") (pin "1") (pinfunction "1_1") (pintype "passive"))
      (node (ref "R29") (pin "1") (pinfunction "1_1") (pintype "passive"))
    )
    (net (code "45") (name "Net-(D3-C)") (class "Default")
      (node (ref "C14") (pin "+") (pinfunction "+_+") (pintype "passive"))
      (node (ref "D3") (pin "K") (pinfunction "C_K") (pintype "passive"))
      (node (ref "IC4") (pin "4") (pinfunction "VDD_4") (pintype "power_in"))
      (node (ref "Q3") (pin "D") (pinfunction "DRAIN_D") (pintype "bidirectional"))
    )
    (net (code "46") (name "Net-(D3-PadA)") (class "Default")
      (node (ref "D3") (pin "A") (pinfunction "A_A") (pintype "passive"))
      (node (ref "R15") (pin "1") (pinfunction "1_1") (pintype "passive"))
    )
    (net (code "47") (name "Net-(D5-C)") (class "Default")
      (node (ref "D5") (pin "K") (pinfunction "C_K") (pintype "passive"))
      (node (ref "R20") (pin "2") (pinfunction "2_2") (pintype "passive"))
    )
    (net (code "48") (name "Net-(F1-1)") (class "Default")
      (node (ref "F1") (pin "P$1") (pinfunction "1_P$1") (pintype "passive"))
      (node (ref "JP2") (pin "1") (pinfunction "1_1") (pintype "passive"))
      (node (ref "SJ2") (pin "1") (pinfunction "1_1") (pintype "passive"))
    )
    (net (code "49") (name "Net-(F1-2)") (class "Default")
      (node (ref "F1") (pin "P$2") (pinfunction "2_P$2") (pintype "passive"))
      (node (ref "JP1") (pin "1") (pinfunction "1_1") (pintype "passive"))
    )
    (net (code "50") (name "Net-(IC2-G)") (class "Default")
      (node (ref "C5") (pin "1") (pinfunction "1_1") (pintype "passive"))
      (node (ref "IC2") (pin "4") (pinfunction "G_4") (pintype "passive"))
      (node (ref "J1") (pin "2") (pinfunction "2_2") (pintype "passive"))
      (node (ref "R3") (pin "1") (pinfunction "1_1") (pintype "passive"))
    )
    (net (code "51") (name "Net-(IC3-BST)") (class "Default")
      (node (ref "C12") (pin "2") (pinfunction "2_2") (pintype "passive"))
      (node (ref "IC3") (pin "2") (pinfunction "BST_2") (pintype "passive"))
    )
    (net (code "52") (name "Net-(IC3-COMP)") (class "Default")
      (node (ref "C10") (pin "1") (pinfunction "1_1") (pintype "passive"))
      (node (ref "IC3") (pin "5") (pinfunction "COMP_5") (pintype "passive"))
    )
    (net (code "53") (name "Net-(IC3-EN)") (class "Default")
      (node (ref "IC3") (pin "8") (pinfunction "EN_8") (pintype "passive"))
      (node (ref "R6") (pin "1") (pinfunction "1_1") (pintype "passive"))
      (node (ref "R7") (pin "2") (pinfunction "2_2") (pintype "passive"))
    )
    (net (code "54") (name "Net-(IC3-FB)") (class "Default")
      (node (ref "IC3") (pin "6") (pinfunction "FB_6") (pintype "passive"))
      (node (ref "R22") (pin "1") (pinfunction "1_1") (pintype "passive"))
      (node (ref "R23") (pin "2") (pinfunction "2_2") (pintype "passive"))
    )
    (net (code "55") (name "Net-(IC3-FSW)") (class "Default")
      (node (ref "IC3") (pin "4") (pinfunction "FSW_4") (pintype "passive"))
      (node (ref "R14") (pin "1") (pinfunction "1_1") (pintype "passive"))
    )
    (net (code "56") (name "Net-(IC3-LX)") (class "Default")
      (node (ref "D4") (pin "C") (pinfunction "C_C") (pintype "passive"))
      (node (ref "IC3") (pin "1") (pinfunction "LX_1") (pintype "passive"))
      (node (ref "L2") (pin "2") (pinfunction "2_2") (pintype "passive"))
      (node (ref "R17") (pin "2") (pinfunction "2_2") (pintype "passive"))
    )
    (net (code "57") (name "Net-(IC3-SS)") (class "Default")
      (node (ref "C11") (pin "1") (pinfunction "1_1") (pintype "passive"))
      (node (ref "IC3") (pin "7") (pinfunction "SS_7") (pintype "passive"))
    )
    (net (code "58") (name "Net-(IC3-VIN)") (class "Default")
      (node (ref "C37") (pin "1") (pinfunction "1_1") (pintype "passive"))
      (node (ref "D2") (pin "C") (pinfunction "C_C") (pintype "passive"))
      (node (ref "IC3") (pin "EX_PAD") (pinfunction "VIN_EX_PAD") (pintype "power_in"))
      (node (ref "R6") (pin "2") (pinfunction "2_2") (pintype "passive"))
    )
    (net (code "59") (name "Net-(IC4-PROG)") (class "Default")
      (node (ref "IC4") (pin "5") (pinfunction "PROG_5") (pintype "passive"))
      (node (ref "R10") (pin "2") (pinfunction "2_2") (pintype "passive"))
    )
    (net (code "60") (name "Net-(IC4-STAT)") (class "Default")
      (node (ref "IC4") (pin "1") (pinfunction "STAT_1") (pintype "passive"))
      (node (ref "R15") (pin "2") (pinfunction "2_2") (pintype "passive"))
      (node (ref "R16") (pin "2") (pinfunction "2_2") (pintype "passive"))
    )
    (net (code "61") (name "Net-(IC6-EN)") (class "Default")
      (node (ref "C7") (pin "1") (pinfunction "1_1") (pintype "passive"))
      (node (ref "C9") (pin "1") (pinfunction "1_1") (pintype "passive"))
      (node (ref "IC2") (pin "5") (pinfunction "D_5") (pintype "passive"))
      (node (ref "IC2") (pin "6") (pinfunction "D_6") (pintype "passive"))
      (node (ref "IC2") (pin "7") (pinfunction "D_7") (pintype "passive"))
      (node (ref "IC2") (pin "8") (pinfunction "D_8") (pintype "passive"))
      (node (ref "IC6") (pin "6") (pinfunction "VBAT_6") (pintype "passive"))
      (node (ref "IC6") (pin "9") (pinfunction "EN_9") (pintype "passive"))
      (node (ref "L1") (pin "2") (pinfunction "2_2") (pintype "passive"))
      (node (ref "R11") (pin "2") (pinfunction "2_2") (pintype "passive"))
    )
    (net (code "62") (name "Net-(IC6-LBI)") (class "Default")
      (node (ref "IC6") (pin "7") (pinfunction "LBI_7") (pintype "passive"))
      (node (ref "R11") (pin "1") (pinfunction "1_1") (pintype "passive"))
      (node (ref "R12") (pin "2") (pinfunction "2_2") (pintype "passive"))
    )
    (net (code "63") (name "Net-(IC6-LBO)") (class "Default")
      (node (ref "IC6") (pin "10") (pinfunction "LBO_10") (pintype "passive"))
      (node (ref "R19") (pin "1") (pinfunction "1_1") (pintype "passive"))
      (node (ref "R20") (pin "1") (pinfunction "1_1") (pintype "passive"))
      (node (ref "R21") (pin "2") (pinfunction "2_2") (pintype "passive"))
    )
    (net (code "64") (name "Net-(IC6-SW-Pad1)") (class "Default")
      (node (ref "IC6") (pin "1") (pinfunction "SW_1") (pintype "passive"))
      (node (ref "IC6") (pin "2") (pinfunction "SW_2") (pintype "passive"))
      (node (ref "L1") (pin "1") (pinfunction "1_1") (pintype "passive"))
    )
    (net (code "65") (name "Net-(IC8-IN1+)") (class "Default")
      (node (ref "IC8") (pin "7") (pinfunction "IN1+_7") (pintype "input"))
      (node (ref "VR1") (pin "2") (pinfunction "2_2") (pintype "passive"))
    )
    (net (code "66") (name "Net-(IC8-IN1-)") (class "Default")
      (node (ref "C21") (pin "+") (pinfunction "+_+") (pintype "passive"))
      (node (ref "IC8") (pin "8") (pinfunction "IN1-_8") (pintype "input"))
    )
    (net (code "67") (name "Net-(IC8-IN2+)") (class "Default")
      (node (ref "IC8") (pin "6") (pinfunction "IN2+_6") (pintype "input"))
      (node (ref "VR2") (pin "2") (pinfunction "2_2") (pintype "passive"))
    )
    (net (code "68") (name "Net-(IC8-IN2-)") (class "Default")
      (node (ref "C22") (pin "+") (pinfunction "+_+") (pintype "passive"))
      (node (ref "IC8") (pin "5") (pinfunction "IN2-_5") (pintype "input"))
    )
    (net (code "69") (name "Net-(IC8-OUT1)") (class "Default")
      (node (ref "C30") (pin "+") (pinfunction "+_+") (pintype "passive"))
      (node (ref "IC8") (pin "1") (pinfunction "OUT1_1") (pintype "output"))
    )
    (net (code "70") (name "Net-(IC8-OUT2)") (class "Default")
      (node (ref "C31") (pin "+") (pinfunction "+_+") (pintype "passive"))
      (node (ref "IC8") (pin "3") (pinfunction "OUT2_3") (pintype "output"))
    )
    (net (code "71") (name "Net-(IC9-VREF)") (class "Default")
      (node (ref "C26") (pin "1") (pinfunction "1_1") (pintype "passive"))
      (node (ref "IC9") (pin "10") (pinfunction "VREF_10") (pintype "passive"))
    )
    (net (code "72") (name "Net-(JP5-Pad4)") (class "Default")
      (node (ref "JP5") (pin "4") (pinfunction "4_4") (pintype "passive"))
      (node (ref "R26") (pin "1") (pinfunction "1_1") (pintype "passive"))
    )
    (net (code "73") (name "Net-(JP5-Pad5)") (class "Default")
      (node (ref "JP5") (pin "5") (pinfunction "5_5") (pintype "passive"))
      (node (ref "R24") (pin "1") (pinfunction "1_1") (pintype "passive"))
    )
    (net (code "74") (name "Net-(LCD1-5V_IN)") (class "Default")
      (node (ref "LCD1") (pin "1") (pinfunction "5V_IN_1") (pintype "passive"))
      (node (ref "SJ1") (pin "2") (pinfunction "2_2") (pintype "passive"))
    )
    (net (code "75") (name "Net-(Q1-OUT)") (class "Default")
      (node (ref "IC5") (pin "2") (pinfunction "2_2") (pintype "bidirectional"))
      (node (ref "Q1") (pin "3") (pinfunction "OUT_3") (pintype "passive"))
      (node (ref "R8") (pin "1") (pinfunction "1_1") (pintype "passive"))
    )
    (net (code "76") (name "Net-(Q2-OUT)") (class "Default")
      (node (ref "IC5") (pin "4") (pinfunction "4_4") (pintype "bidirectional"))
      (node (ref "Q2") (pin "3") (pinfunction "OUT_3") (pintype "passive"))
      (node (ref "R13") (pin "1") (pinfunction "1_1") (pintype "passive"))
    )
    (net (code "77") (name "Net-(Q3-GATE)") (class "Default")
      (node (ref "Q3") (pin "G") (pinfunction "GATE_G") (pintype "bidirectional"))
      (node (ref "Q4") (pin "3") (pinfunction "OUT_3") (pintype "passive"))
      (node (ref "R18") (pin "2") (pinfunction "2_2") (pintype "passive"))
    )
    (net (code "78") (name "Net-(U$1-GPIO4{slash}GPCLK0)") (class "Default")
      (node (ref "C1") (pin "1") (pinfunction "1_1") (pintype "passive"))
      (node (ref "SW2") (pin "1") (pinfunction "1_1") (pintype "passive"))
      (node (ref "U$1") (pin "P1_7") (pinfunction "GPIO4/GPCLK0_P1_7") (pintype "bidirectional"))
    )
    (net (code "79") (name "Net-(U$1-RESET)") (class "Default")
      (node (ref "C2") (pin "1") (pinfunction "1_1") (pintype "passive"))
      (node (ref "SW1") (pin "2") (pinfunction "2_2") (pintype "passive"))
      (node (ref "U$1") (pin "P6_1") (pinfunction "RESET_P6_1") (pintype "power_in"))
    )
    (net (code "80") (name "Net-(ZD2-K)") (class "Default")
      (node (ref "IC5") (pin "7") (pinfunction "7_7") (pintype "output"))
      (node (ref "IC5") (pin "8") (pinfunction "8_8") (pintype "output"))
      (node (ref "JP3") (pin "2") (pinfunction "2_2") (pintype "passive"))
      (node (ref "ZD2") (pin "C") (pinfunction "K_C") (pintype "passive"))
    )
    (net (code "81") (name "Net-(ZD3-K)") (class "Default")
      (node (ref "IC5") (pin "5") (pinfunction "5_5") (pintype "output"))
      (node (ref "IC5") (pin "6") (pinfunction "6_6") (pintype "output"))
      (node (ref "JP3") (pin "1") (pinfunction "1_1") (pintype "passive"))
      (node (ref "ZD3") (pin "C") (pinfunction "K_C") (pintype "passive"))
    )
    (net (code "82") (name "unconnected-(IC1-SDO-Pad6)") (class "Default")
      (node (ref "IC1") (pin "6") (pinfunction "SDO_6") (pintype "output"))
    )
    (net (code "83") (name "unconnected-(IC6-FB-Pad12)") (class "Default")
      (node (ref "IC6") (pin "12") (pinfunction "FB_12") (pintype "passive"))
    )
    (net (code "84") (name "unconnected-(IC6-NC-Pad16)") (class "Default")
      (node (ref "IC6") (pin "16") (pinfunction "NC_16") (pintype "no_connect"))
    )
    (net (code "85") (name "unconnected-(J2-Pad4)") (class "Default")
      (node (ref "J2") (pin "4") (pinfunction "4_4") (pintype "passive"))
    )
    (net (code "86") (name "unconnected-(LCD1-3V3_OUT-Pad21)") (class "Default")
      (node (ref "LCD1") (pin "21") (pinfunction "3V3_OUT_21") (pintype "passive"))
    )
    (net (code "87") (name "unconnected-(LCD1-NC-Pad7)") (class "Default")
      (node (ref "LCD1") (pin "7") (pinfunction "NC_7") (pintype "no_connect"))
    )
    (net (code "88") (name "unconnected-(LCD1-NC-Pad8)") (class "Default")
      (node (ref "LCD1") (pin "8") (pinfunction "NC_8") (pintype "no_connect"))
    )
    (net (code "89") (name "unconnected-(LCD1-NC-Pad9)") (class "Default")
      (node (ref "LCD1") (pin "9") (pinfunction "NC_9") (pintype "no_connect"))
    )
    (net (code "90") (name "unconnected-(LCD1-NC-Pad10)") (class "Default")
      (node (ref "LCD1") (pin "10") (pinfunction "NC_10") (pintype "no_connect"))
    )
    (net (code "91") (name "unconnected-(LCD1-NC-Pad11)") (class "Default")
      (node (ref "LCD1") (pin "11") (pinfunction "NC_11") (pintype "no_connect"))
    )
    (net (code "92") (name "unconnected-(LCD1-NC-Pad12)") (class "Default")
      (node (ref "LCD1") (pin "12") (pinfunction "NC_12") (pintype "no_connect"))
    )
    (net (code "93") (name "unconnected-(LCD1-NC-Pad13)") (class "Default")
      (node (ref "LCD1") (pin "13") (pinfunction "NC_13") (pintype "no_connect"))
    )
    (net (code "94") (name "unconnected-(LCD1-NC-Pad14)") (class "Default")
      (node (ref "LCD1") (pin "14") (pinfunction "NC_14") (pintype "no_connect"))
    )
    (net (code "95") (name "unconnected-(LCD1-NC-Pad16)") (class "Default")
      (node (ref "LCD1") (pin "16") (pinfunction "NC_16") (pintype "no_connect"))
    )
    (net (code "96") (name "unconnected-(LCD1-NC-Pad17)") (class "Default")
      (node (ref "LCD1") (pin "17") (pinfunction "NC_17") (pintype "no_connect"))
    )
    (net (code "97") (name "unconnected-(LCD1-NC-Pad18)") (class "Default")
      (node (ref "LCD1") (pin "18") (pinfunction "NC_18") (pintype "no_connect"))
    )
    (net (code "98") (name "unconnected-(LCD1-NC-Pad23)") (class "Default")
      (node (ref "LCD1") (pin "23") (pinfunction "NC_23") (pintype "no_connect"))
    )
    (net (code "99") (name "unconnected-(LCD1-NC-Pad24)") (class "Default")
      (node (ref "LCD1") (pin "24") (pinfunction "NC_24") (pintype "no_connect"))
    )
    (net (code "100") (name "unconnected-(LCD1-NC-Pad25)") (class "Default")
      (node (ref "LCD1") (pin "25") (pinfunction "NC_25") (pintype "no_connect"))
    )
    (net (code "101") (name "unconnected-(LCD1-NC-Pad26)") (class "Default")
      (node (ref "LCD1") (pin "26") (pinfunction "NC_26") (pintype "no_connect"))
    )
    (net (code "102") (name "unconnected-(LCD1-NC-Pad27)") (class "Default")
      (node (ref "LCD1") (pin "27") (pinfunction "NC_27") (pintype "no_connect"))
    )
    (net (code "103") (name "unconnected-(LCD1-NC-Pad28)") (class "Default")
      (node (ref "LCD1") (pin "28") (pinfunction "NC_28") (pintype "no_connect"))
    )
    (net (code "104") (name "unconnected-(LCD1-NC-Pad29)") (class "Default")
      (node (ref "LCD1") (pin "29") (pinfunction "NC_29") (pintype "no_connect"))
    )
    (net (code "105") (name "unconnected-(LCD1-NC-Pad30)") (class "Default")
      (node (ref "LCD1") (pin "30") (pinfunction "NC_30") (pintype "no_connect"))
    )
    (net (code "106") (name "unconnected-(LCD1-NC-Pad31)") (class "Default")
      (node (ref "LCD1") (pin "31") (pinfunction "NC_31") (pintype "no_connect"))
    )
    (net (code "107") (name "unconnected-(LCD1-NC-Pad37)") (class "Default")
      (node (ref "LCD1") (pin "37") (pinfunction "NC_37") (pintype "no_connect"))
    )
    (net (code "108") (name "unconnected-(LCD1-NC-Pad38)") (class "Default")
      (node (ref "LCD1") (pin "38") (pinfunction "NC_38") (pintype "no_connect"))
    )
    (net (code "109") (name "unconnected-(U1-KEY-Pad26)") (class "Default")
      (node (ref "U1") (pin "26") (pinfunction "KEY_26") (pintype "input"))
    )
    (net (code "110") (name "unconnected-(U1-LED-Pad24)") (class "Default")
      (node (ref "U1") (pin "24") (pinfunction "LED_24") (pintype "output"))
    )
  )
)
